# MCU.net
KiCad netlist of a schematic drawn in Altium Designer
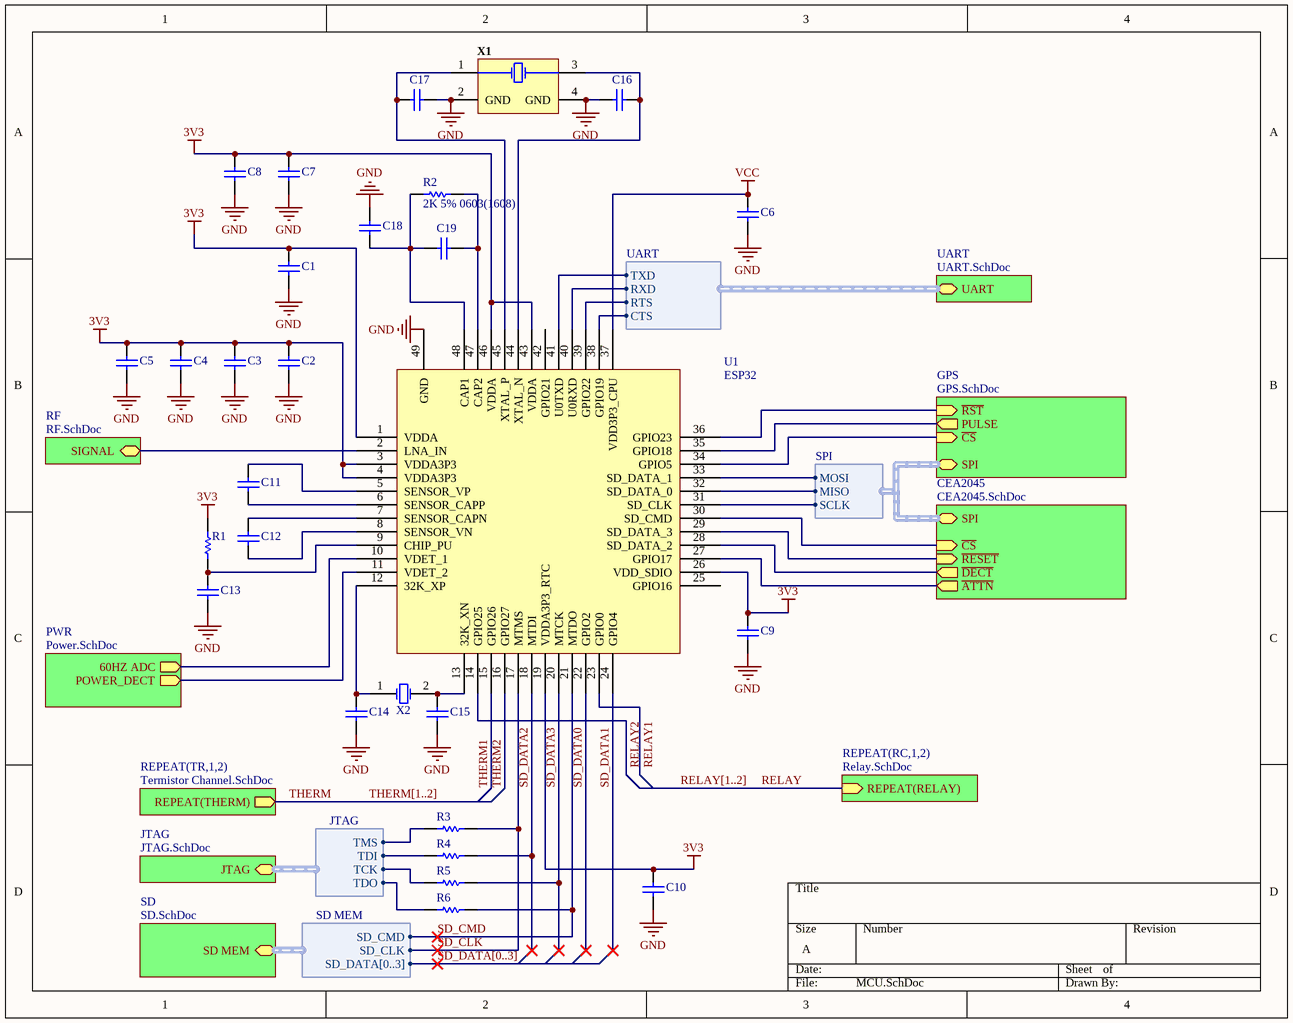
[diagram p0: MCU.SchDoc]

(export (version "E")
  (design (tool "Eeschema 10.0.6"))
  (components
    (comp (ref "C1")
      (value "CAP 100nF 6.3V 0603(1608)")
      (footprint "CAPC0603(1608)100_M")
      (description "CAP 100nF 6.3V ±5% 0603 (1608 Metric) Thickness 1mm SMD")
      (fields (field (name "TOLERANCE") "Â±5%"))
      (libsource (lib "Altium Content Vault") (part "CMP-1035-02575-1"))
    )
    (comp (ref "C2")
      (value "CAP 100nF 6.3V 0603(1608)")
      (footprint "CAPC0603(1608)100_M")
      (description "CAP 100nF 6.3V ±5% 0603 (1608 Metric) Thickness 1mm SMD")
      (fields (field (name "TOLERANCE") "Â±5%"))
      (libsource (lib "Altium Content Vault") (part "CMP-1035-02575-1"))
    )
    (comp (ref "C3")
      (value "CAP 10uF 6.3V 1210(3225)")
      (footprint "CAPC1210(3225)170_L")
      (description "CAP 10uF 6.3V ±10% 1210 (3225 Metric) Thickness 1.7mm SMD")
      (fields (field (name "TOLERANCE") "Â±10%"))
      (libsource (lib "Altium Content Vault") (part "CMP-1038-02188-1"))
    )
    (comp (ref "C4")
      (value "CAP 10uF 6.3V 1210(3225)")
      (footprint "CAPC1210(3225)170_L")
      (description "CAP 10uF 6.3V ±10% 1210 (3225 Metric) Thickness 1.7mm SMD")
      (fields (field (name "TOLERANCE") "Â±10%"))
      (libsource (lib "Altium Content Vault") (part "CMP-1038-02188-1"))
    )
    (comp (ref "C5")
      (value "CAP 1uF 6.3V 0603(1608)")
      (footprint "CAPC0603(1608)100_N")
      (description "CAP 1uF 6.3V ±10% 0603 (1608 Metric) Thickness 1mm SMD")
      (fields (field (name "TOLERANCE") "Â±10%"))
      (libsource (lib "Altium Content Vault") (part "CMP-1035-02730-1"))
    )
    (comp (ref "C6")
      (value "CAP 100nF 6.3V 0603(1608)")
      (footprint "CAPC0603(1608)100_M")
      (description "CAP 100nF 6.3V ±5% 0603 (1608 Metric) Thickness 1mm SMD")
      (fields (field (name "TOLERANCE") "Â±5%"))
      (libsource (lib "Altium Content Vault") (part "CMP-1035-02575-1"))
    )
    (comp (ref "C7")
      (value "CAP 1uF 6.3V 0603(1608)")
      (footprint "CAPC0603(1608)100_N")
      (description "CAP 1uF 6.3V ±10% 0603 (1608 Metric) Thickness 1mm SMD")
      (fields (field (name "TOLERANCE") "Â±10%"))
      (libsource (lib "Altium Content Vault") (part "CMP-1035-02730-1"))
    )
    (comp (ref "C8")
      (value "CAP 100pF 10V 0603(1608)")
      (footprint "CAPC0603(1608)100_N")
      (description "CAP 100pF 10V ±10% 0603 (1608 Metric) Thickness 1mm SMD")
      (fields (field (name "TOLERANCE") "Â±10%"))
      (libsource (lib "Altium Content Vault") (part "CMP-1035-01255-1"))
    )
    (comp (ref "C9")
      (value "CAP 1uF 6.3V 0603(1608)")
      (footprint "CAPC0603(1608)100_N")
      (description "CAP 1uF 6.3V ±10% 0603 (1608 Metric) Thickness 1mm SMD")
      (fields (field (name "TOLERANCE") "Â±10%"))
      (libsource (lib "Altium Content Vault") (part "CMP-1035-02730-1"))
    )
    (comp (ref "C10")
      (value "CAP 100nF 6.3V 0603(1608)")
      (footprint "CAPC0603(1608)100_M")
      (description "CAP 100nF 6.3V ±5% 0603 (1608 Metric) Thickness 1mm SMD")
      (fields (field (name "TOLERANCE") "Â±5%"))
      (libsource (lib "Altium Content Vault") (part "CMP-1035-02575-1"))
    )
    (comp (ref "C11")
      (value "CAP 220pF 6.3V 0603(1608)")
      (footprint "CAPC0603(1608)100_N")
      (description "CAP 220pF 6.3V ±10% 0603 (1608 Metric) Thickness 1mm SMD")
      (fields (field (name "TOLERANCE") "Â±10%"))
      (libsource (lib "Altium Content Vault") (part "CMP-1035-01452-1"))
    )
    (comp (ref "C12")
      (value "CAP 100nF 6.3V 0603(1608)")
      (footprint "CAPC0603(1608)100_M")
      (description "CAP 100nF 6.3V ±5% 0603 (1608 Metric) Thickness 1mm SMD")
      (fields (field (name "TOLERANCE") "Â±5%"))
      (libsource (lib "Altium Content Vault") (part "CMP-1035-02575-1"))
    )
    (comp (ref "C13")
      (value "CAP 100nF 6.3V 0603(1608)")
      (footprint "CAPC0603(1608)100_M")
      (description "CAP 100nF 6.3V ±5% 0603 (1608 Metric) Thickness 1mm SMD")
      (fields (field (name "TOLERANCE") "Â±5%"))
      (libsource (lib "Altium Content Vault") (part "CMP-1035-02575-1"))
    )
    (comp (ref "C14")
      (value "CAP 12pF 16V 0603(1608)")
      (footprint "CAPC0603(1608)100_M")
      (description "CAP 12pF 16V ±10% 0603 (1608 Metric) Thickness 1mm SMD")
      (fields (field (name "TOLERANCE") "Â±10%"))
      (libsource (lib "Altium Content Vault") (part "CMP-1035-00607-1"))
    )
    (comp (ref "C15")
      (value "CAP 12pF 16V 0603(1608)")
      (footprint "CAPC0603(1608)100_M")
      (description "CAP 12pF 16V ±10% 0603 (1608 Metric) Thickness 1mm SMD")
      (fields (field (name "TOLERANCE") "Â±10%"))
      (libsource (lib "Altium Content Vault") (part "CMP-1035-00607-1"))
    )
    (comp (ref "C16")
      (value "CAP 22pF 16V 0603(1608)")
      (footprint "CAPC0603(1608)100_M")
      (description "CAP 22pF 16V ±10% 0603 (1608 Metric) Thickness 1mm SMD")
      (fields (field (name "TOLERANCE") "Â±10%"))
      (libsource (lib "Altium Content Vault") (part "CMP-1035-00809-1"))
    )
    (comp (ref "C17")
      (value "CAP 10pF 10V 0603(1608)")
      (footprint "CAPC0603(1608)100_M")
      (description "CAP 10pF 10V ±10% 0603 (1608 Metric) Thickness 1mm SMD")
      (fields (field (name "TOLERANCE") "Â±10%"))
      (libsource (lib "Altium Content Vault") (part "CMP-1035-00539-1"))
    )
    (comp (ref "C18")
      (value "CAP 10nF 6.3V 0603(1608)")
      (footprint "CAPC0603(1608)100_M")
      (description "CAP 10nF 6.3V ±10% 0603 (1608 Metric) Thickness 1mm SMD")
      (fields (field (name "TOLERANCE") "Â±10%"))
      (libsource (lib "Altium Content Vault") (part "CMP-1035-02302-1"))
    )
    (comp (ref "C19")
      (value "CAP 3.3nF 6.3V 0603(1608)")
      (footprint "CAPC0603(1608)100_L")
      (description "CAP 3.3nF 6.3V ±10% 0603 (1608 Metric) Thickness 1mm SMD")
      (fields (field (name "TOLERANCE") "Â±10%"))
      (libsource (lib "Altium Content Vault") (part "CMP-1035-02104-1"))
    )
    (comp (ref "R1")
      (value "1K 5% 0603(1608)")
      (footprint "RESC0603(1608)_L")
      (description "1K 0.1W 5% 0603 (1608 Metric)  SMD")
      (fields (field (name "POWER") "0.1 W") (field (name "TOLERANCE") "5 %"))
      (libsource (lib "Altium Content Vault") (part "CMP-1012-00074-1"))
    )
    (comp (ref "R2")
      (value "2K 5% 0603(1608)")
      (footprint "RESC0603(1608)_N")
      (description "2K 0.1W 5% 0603 (1608 Metric)  SMD")
      (fields (field (name "TOLERANCE") "5 %") (field (name "POWER") "0.1 W"))
      (libsource (lib "Altium Content Vault") (part "RES"))
    )
    (comp (ref "R3")
      (value "100R 5% 0603(1608)")
      (footprint "RESC0603(1608)_L")
      (description "100R 0.1W 5% 0603 (1608 Metric)  SMD")
      (fields (field (name "POWER") "0.1 W") (field (name "TOLERANCE") "5 %"))
      (libsource (lib "Altium Content Vault") (part "CMP-1012-00050-1"))
    )
    (comp (ref "R4")
      (value "100R 5% 0603(1608)")
      (footprint "RESC0603(1608)_L")
      (description "100R 0.1W 5% 0603 (1608 Metric)  SMD")
      (fields (field (name "POWER") "0.1 W") (field (name "TOLERANCE") "5 %"))
      (libsource (lib "Altium Content Vault") (part "CMP-1012-00050-1"))
    )
    (comp (ref "R5")
      (value "100R 5% 0603(1608)")
      (footprint "RESC0603(1608)_L")
      (description "100R 0.1W 5% 0603 (1608 Metric)  SMD")
      (fields (field (name "POWER") "0.1 W") (field (name "TOLERANCE") "5 %"))
      (libsource (lib "Altium Content Vault") (part "CMP-1012-00050-1"))
    )
    (comp (ref "R6")
      (value "100R 5% 0603(1608)")
      (footprint "RESC0603(1608)_L")
      (description "100R 0.1W 5% 0603 (1608 Metric)  SMD")
      (fields (field (name "POWER") "0.1 W") (field (name "TOLERANCE") "5 %"))
      (libsource (lib "Altium Content Vault") (part "CMP-1012-00050-1"))
    )
    (comp (ref "U1")
      (value "ESP32")
      (footprint "QFN40P600X600X90_HS-49N")
      (libsource (lib "Water Heater Components") (part "ESP32"))
    )
    (comp (ref "X1")
      (value "7B-40.000MAAJ-T")
      (footprint "TXC-7B-4_V")
      (description "9B Series Quartz Crystal, 40 MHz, +/-30 ppm, 18 pF, -40 to 85 degC, 4-Pin SMD, RoHS, Tape and Reel")
      (fields (field (name "TOLERANCE") "1%"))
      (libsource (lib "Altium Content Vault") (part "CMP-1774-00003-1"))
    )
    (comp (ref "X2")
      (value "14340272-32.768KHz")
      (footprint "ITTI-14340272-32.768KHz-2_V")
      (description "Crystal, 32.768 KHz, -40 to 85 degC, 3.2 x 1.5 x 0.9 mm SMD")
      (fields (field (name "MANUFACTURER") "ITTI"))
      (libsource (lib "Altium Content Vault") (part "CMP-0463-00001-2"))
    )
  )
  (nets
    (net (code "6") (name "/60HZ ADC") (class "Default")
      (node (ref "U1") (pin "10") (pinfunction "VDET_1_10") (pintype "passive"))
    )
    (net (code "7") (name "/POWER_DECT") (class "Default")
      (node (ref "U1") (pin "11") (pinfunction "VDET_2_11") (pintype "passive"))
    )
    (net (code "8") (name "/PULSE") (class "Default")
      (node (ref "U1") (pin "35") (pinfunction "GPIO18_35") (pintype "passive"))
    )
    (net (code "10") (name "/RELAY1") (class "Default")
      (node (ref "U1") (pin "23") (pinfunction "GPIO0_23") (pintype "passive"))
    )
    (net (code "11") (name "/RELAY2") (class "Default")
      (node (ref "U1") (pin "14") (pinfunction "GPIO25_14") (pintype "passive"))
    )
    (net (code "15") (name "/SD_DATA0") (class "Default")
      (node (ref "U1") (pin "22") (pinfunction "GPIO2_22") (pintype "passive+no_connect"))
    )
    (net (code "16") (name "/SD_DATA1") (class "Default")
      (node (ref "U1") (pin "24") (pinfunction "GPIO4_24") (pintype "passive+no_connect"))
    )
    (net (code "17") (name "/SD_DATA2") (class "Default")
      (node (ref "R4") (pin "2") (pinfunction "2_2") (pintype "passive"))
      (node (ref "U1") (pin "18") (pinfunction "MTDI_18") (pintype "passive"))
    )
    (net (code "18") (name "/SD_DATA3") (class "Default")
      (node (ref "R5") (pin "2") (pinfunction "2_2") (pintype "passive"))
      (node (ref "U1") (pin "20") (pinfunction "MTCK_20") (pintype "passive"))
    )
    (net (code "20") (name "/SIGNAL") (class "Default")
      (node (ref "U1") (pin "2") (pinfunction "LNA_IN_2") (pintype "passive"))
    )
    (net (code "22") (name "/THERM1") (class "Default")
      (node (ref "U1") (pin "15") (pinfunction "GPIO26_15") (pintype "passive"))
    )
    (net (code "23") (name "/THERM2") (class "Default")
      (node (ref "U1") (pin "16") (pinfunction "GPIO27_16") (pintype "passive"))
    )
    (net (code "29") (name "/~{ATTN}") (class "Default")
      (node (ref "U1") (pin "27") (pinfunction "GPIO17_27") (pintype "passive"))
    )
    (net (code "30") (name "/~{CS}") (class "Default")
      (node (ref "U1") (pin "30") (pinfunction "SD_CMD_30") (pintype "passive"))
    )
    (net (code "31") (name "/~{CS}_1") (class "Default")
      (node (ref "U1") (pin "34") (pinfunction "GPIO5_34") (pintype "passive"))
    )
    (net (code "32") (name "/~{DECT}") (class "Default")
      (node (ref "U1") (pin "28") (pinfunction "SD_DATA_2_28") (pintype "passive"))
    )
    (net (code "33") (name "/~{RESET}") (class "Default")
      (node (ref "U1") (pin "29") (pinfunction "SD_DATA_3_29") (pintype "passive"))
    )
    (net (code "34") (name "/~{RST}") (class "Default")
      (node (ref "U1") (pin "36") (pinfunction "GPIO23_36") (pintype "passive"))
    )
    (net (code "35") (name "3V3") (class "Default")
      (node (ref "C1") (pin "2") (pinfunction "2_2") (pintype "passive"))
      (node (ref "C10") (pin "2") (pinfunction "2_2") (pintype "passive"))
      (node (ref "C2") (pin "2") (pinfunction "2_2") (pintype "passive"))
      (node (ref "C3") (pin "2") (pinfunction "2_2") (pintype "passive"))
      (node (ref "C4") (pin "2") (pinfunction "2_2") (pintype "passive"))
      (node (ref "C5") (pin "1") (pinfunction "1_1") (pintype "passive"))
      (node (ref "C7") (pin "1") (pinfunction "1_1") (pintype "passive"))
      (node (ref "C8") (pin "2") (pinfunction "2_2") (pintype "passive"))
      (node (ref "C9") (pin "1") (pinfunction "1_1") (pintype "passive"))
      (node (ref "R1") (pin "2") (pinfunction "2_2") (pintype "passive"))
      (node (ref "U1") (pin "1") (pinfunction "VDDA_1") (pintype "passive"))
      (node (ref "U1") (pin "19") (pinfunction "VDDA3P3_RTC_19") (pintype "passive"))
      (node (ref "U1") (pin "26") (pinfunction "VDD_SDIO_26") (pintype "passive"))
      (node (ref "U1") (pin "3") (pinfunction "VDDA3P3_3") (pintype "passive"))
      (node (ref "U1") (pin "4") (pinfunction "VDDA3P3_4") (pintype "passive"))
      (node (ref "U1") (pin "43") (pinfunction "VDDA_43") (pintype "passive"))
      (node (ref "U1") (pin "46") (pinfunction "VDDA_46") (pintype "passive"))
    )
    (net (code "36") (name "GND") (class "Default")
      (node (ref "C1") (pin "1") (pinfunction "1_1") (pintype "passive"))
      (node (ref "C10") (pin "1") (pinfunction "1_1") (pintype "passive"))
      (node (ref "C13") (pin "1") (pinfunction "1_1") (pintype "passive"))
      (node (ref "C14") (pin "1") (pinfunction "1_1") (pintype "passive"))
      (node (ref "C15") (pin "1") (pinfunction "1_1") (pintype "passive"))
      (node (ref "C16") (pin "1") (pinfunction "1_1") (pintype "passive"))
      (node (ref "C17") (pin "1") (pinfunction "1_1") (pintype "passive"))
      (node (ref "C18") (pin "2") (pinfunction "2_2") (pintype "passive"))
      (node (ref "C2") (pin "1") (pinfunction "1_1") (pintype "passive"))
      (node (ref "C3") (pin "1") (pinfunction "1_1") (pintype "passive"))
      (node (ref "C4") (pin "1") (pinfunction "1_1") (pintype "passive"))
      (node (ref "C5") (pin "2") (pinfunction "2_2") (pintype "passive"))
      (node (ref "C6") (pin "1") (pinfunction "1_1") (pintype "passive"))
      (node (ref "C7") (pin "2") (pinfunction "2_2") (pintype "passive"))
      (node (ref "C8") (pin "1") (pinfunction "1_1") (pintype "passive"))
      (node (ref "C9") (pin "2") (pinfunction "2_2") (pintype "passive"))
      (node (ref "U1") (pin "49") (pinfunction "GND_49") (pintype "passive"))
      (node (ref "X1") (pin "2") (pinfunction "GND_2") (pintype "power_in"))
      (node (ref "X1") (pin "4") (pinfunction "GND_4") (pintype "power_in"))
    )
    (net (code "37") (name "Net-(U1-32K_XN)") (class "Default")
      (node (ref "C15") (pin "2") (pinfunction "2_2") (pintype "passive"))
      (node (ref "U1") (pin "13") (pinfunction "32K_XN_13") (pintype "passive"))
      (node (ref "X2") (pin "2") (pinfunction "X2_2") (pintype "passive"))
    )
    (net (code "38") (name "Net-(U1-32K_XP)") (class "Default")
      (node (ref "C14") (pin "2") (pinfunction "2_2") (pintype "passive"))
      (node (ref "U1") (pin "12") (pinfunction "32K_XP_12") (pintype "passive"))
      (node (ref "X2") (pin "1") (pinfunction "X1_1") (pintype "passive"))
    )
    (net (code "39") (name "Net-(U1-CAP1)") (class "Default")
      (node (ref "C18") (pin "1") (pinfunction "1_1") (pintype "passive"))
      (node (ref "C19") (pin "1") (pinfunction "1_1") (pintype "passive"))
      (node (ref "R2") (pin "1") (pinfunction "1_1") (pintype "passive"))
      (node (ref "U1") (pin "48") (pinfunction "CAP1_48") (pintype "passive"))
    )
    (net (code "40") (name "Net-(U1-CAP2)") (class "Default")
      (node (ref "C19") (pin "2") (pinfunction "2_2") (pintype "passive"))
      (node (ref "R2") (pin "2") (pinfunction "2_2") (pintype "passive"))
      (node (ref "U1") (pin "47") (pinfunction "CAP2_47") (pintype "passive"))
    )
    (net (code "41") (name "Net-(U1-CHIP_PU)") (class "Default")
      (node (ref "C13") (pin "2") (pinfunction "2_2") (pintype "passive"))
      (node (ref "R1") (pin "1") (pinfunction "1_1") (pintype "passive"))
      (node (ref "U1") (pin "9") (pinfunction "CHIP_PU_9") (pintype "passive"))
    )
    (net (code "42") (name "Net-(U1-MTDO)") (class "Default")
      (node (ref "R6") (pin "2") (pinfunction "2_2") (pintype "passive"))
      (node (ref "U1") (pin "21") (pinfunction "MTDO_21") (pintype "passive"))
    )
    (net (code "43") (name "Net-(U1-MTMS)") (class "Default")
      (node (ref "R3") (pin "2") (pinfunction "2_2") (pintype "passive"))
      (node (ref "U1") (pin "17") (pinfunction "MTMS_17") (pintype "passive"))
    )
    (net (code "44") (name "Net-(U1-SENSOR_CAPN)") (class "Default")
      (node (ref "C12") (pin "2") (pinfunction "2_2") (pintype "passive"))
      (node (ref "U1") (pin "7") (pinfunction "SENSOR_CAPN_7") (pintype "passive"))
    )
    (net (code "45") (name "Net-(U1-SENSOR_CAPP)") (class "Default")
      (node (ref "C11") (pin "1") (pinfunction "1_1") (pintype "passive"))
      (node (ref "U1") (pin "6") (pinfunction "SENSOR_CAPP_6") (pintype "passive"))
    )
    (net (code "46") (name "Net-(U1-SENSOR_VN)") (class "Default")
      (node (ref "C12") (pin "1") (pinfunction "1_1") (pintype "passive"))
      (node (ref "U1") (pin "8") (pinfunction "SENSOR_VN_8") (pintype "passive"))
    )
    (net (code "47") (name "Net-(U1-SENSOR_VP)") (class "Default")
      (node (ref "C11") (pin "2") (pinfunction "2_2") (pintype "passive"))
      (node (ref "U1") (pin "5") (pinfunction "SENSOR_VP_5") (pintype "passive"))
    )
    (net (code "48") (name "Net-(U1-XTAL_N)") (class "Default")
      (node (ref "C16") (pin "2") (pinfunction "2_2") (pintype "passive"))
      (node (ref "U1") (pin "44") (pinfunction "XTAL_N_44") (pintype "passive"))
      (node (ref "X1") (pin "3") (pinfunction "X2_3") (pintype "passive"))
    )
    (net (code "49") (name "Net-(U1-XTAL_P)") (class "Default")
      (node (ref "C17") (pin "2") (pinfunction "2_2") (pintype "passive"))
      (node (ref "U1") (pin "45") (pinfunction "XTAL_P_45") (pintype "passive"))
      (node (ref "X1") (pin "1") (pinfunction "X1_1") (pintype "passive"))
    )
    (net (code "50") (name "VCC") (class "Default")
      (node (ref "C6") (pin "2") (pinfunction "2_2") (pintype "passive"))
      (node (ref "U1") (pin "37") (pinfunction "VDD3P3_CPU_37") (pintype "passive"))
    )
    (net (code "51") (name "unconnected-(R3-Pad1)") (class "Default")
      (node (ref "R3") (pin "1") (pinfunction "1_1") (pintype "passive"))
    )
    (net (code "52") (name "unconnected-(R4-Pad1)") (class "Default")
      (node (ref "R4") (pin "1") (pinfunction "1_1") (pintype "passive"))
    )
    (net (code "53") (name "unconnected-(R5-Pad1)") (class "Default")
      (node (ref "R5") (pin "1") (pinfunction "1_1") (pintype "passive"))
    )
    (net (code "54") (name "unconnected-(R6-Pad1)") (class "Default")
      (node (ref "R6") (pin "1") (pinfunction "1_1") (pintype "passive"))
    )
    (net (code "55") (name "unconnected-(U1-GPIO16-Pad25)") (class "Default")
      (node (ref "U1") (pin "25") (pinfunction "GPIO16_25") (pintype "passive"))
    )
    (net (code "56") (name "unconnected-(U1-GPIO19-Pad38)") (class "Default")
      (node (ref "U1") (pin "38") (pinfunction "GPIO19_38") (pintype "passive"))
    )
    (net (code "57") (name "unconnected-(U1-GPIO21-Pad42)") (class "Default")
      (node (ref "U1") (pin "42") (pinfunction "GPIO21_42") (pintype "passive"))
    )
    (net (code "58") (name "unconnected-(U1-GPIO22-Pad39)") (class "Default")
      (node (ref "U1") (pin "39") (pinfunction "GPIO22_39") (pintype "passive"))
    )
    (net (code "59") (name "unconnected-(U1-SD_CLK-Pad31)") (class "Default")
      (node (ref "U1") (pin "31") (pinfunction "SD_CLK_31") (pintype "passive"))
    )
    (net (code "60") (name "unconnected-(U1-SD_DATA_0-Pad32)") (class "Default")
      (node (ref "U1") (pin "32") (pinfunction "SD_DATA_0_32") (pintype "passive"))
    )
    (net (code "61") (name "unconnected-(U1-SD_DATA_1-Pad33)") (class "Default")
      (node (ref "U1") (pin "33") (pinfunction "SD_DATA_1_33") (pintype "passive"))
    )
    (net (code "62") (name "unconnected-(U1-U0RXD-Pad40)") (class "Default")
      (node (ref "U1") (pin "40") (pinfunction "U0RXD_40") (pintype "passive"))
    )
    (net (code "63") (name "unconnected-(U1-U0TXD-Pad41)") (class "Default")
      (node (ref "U1") (pin "41") (pinfunction "U0TXD_41") (pintype "passive"))
    )
  )
)
